# OPA_1_1.net
KiCad netlist of a schematic drawn in EAGLE
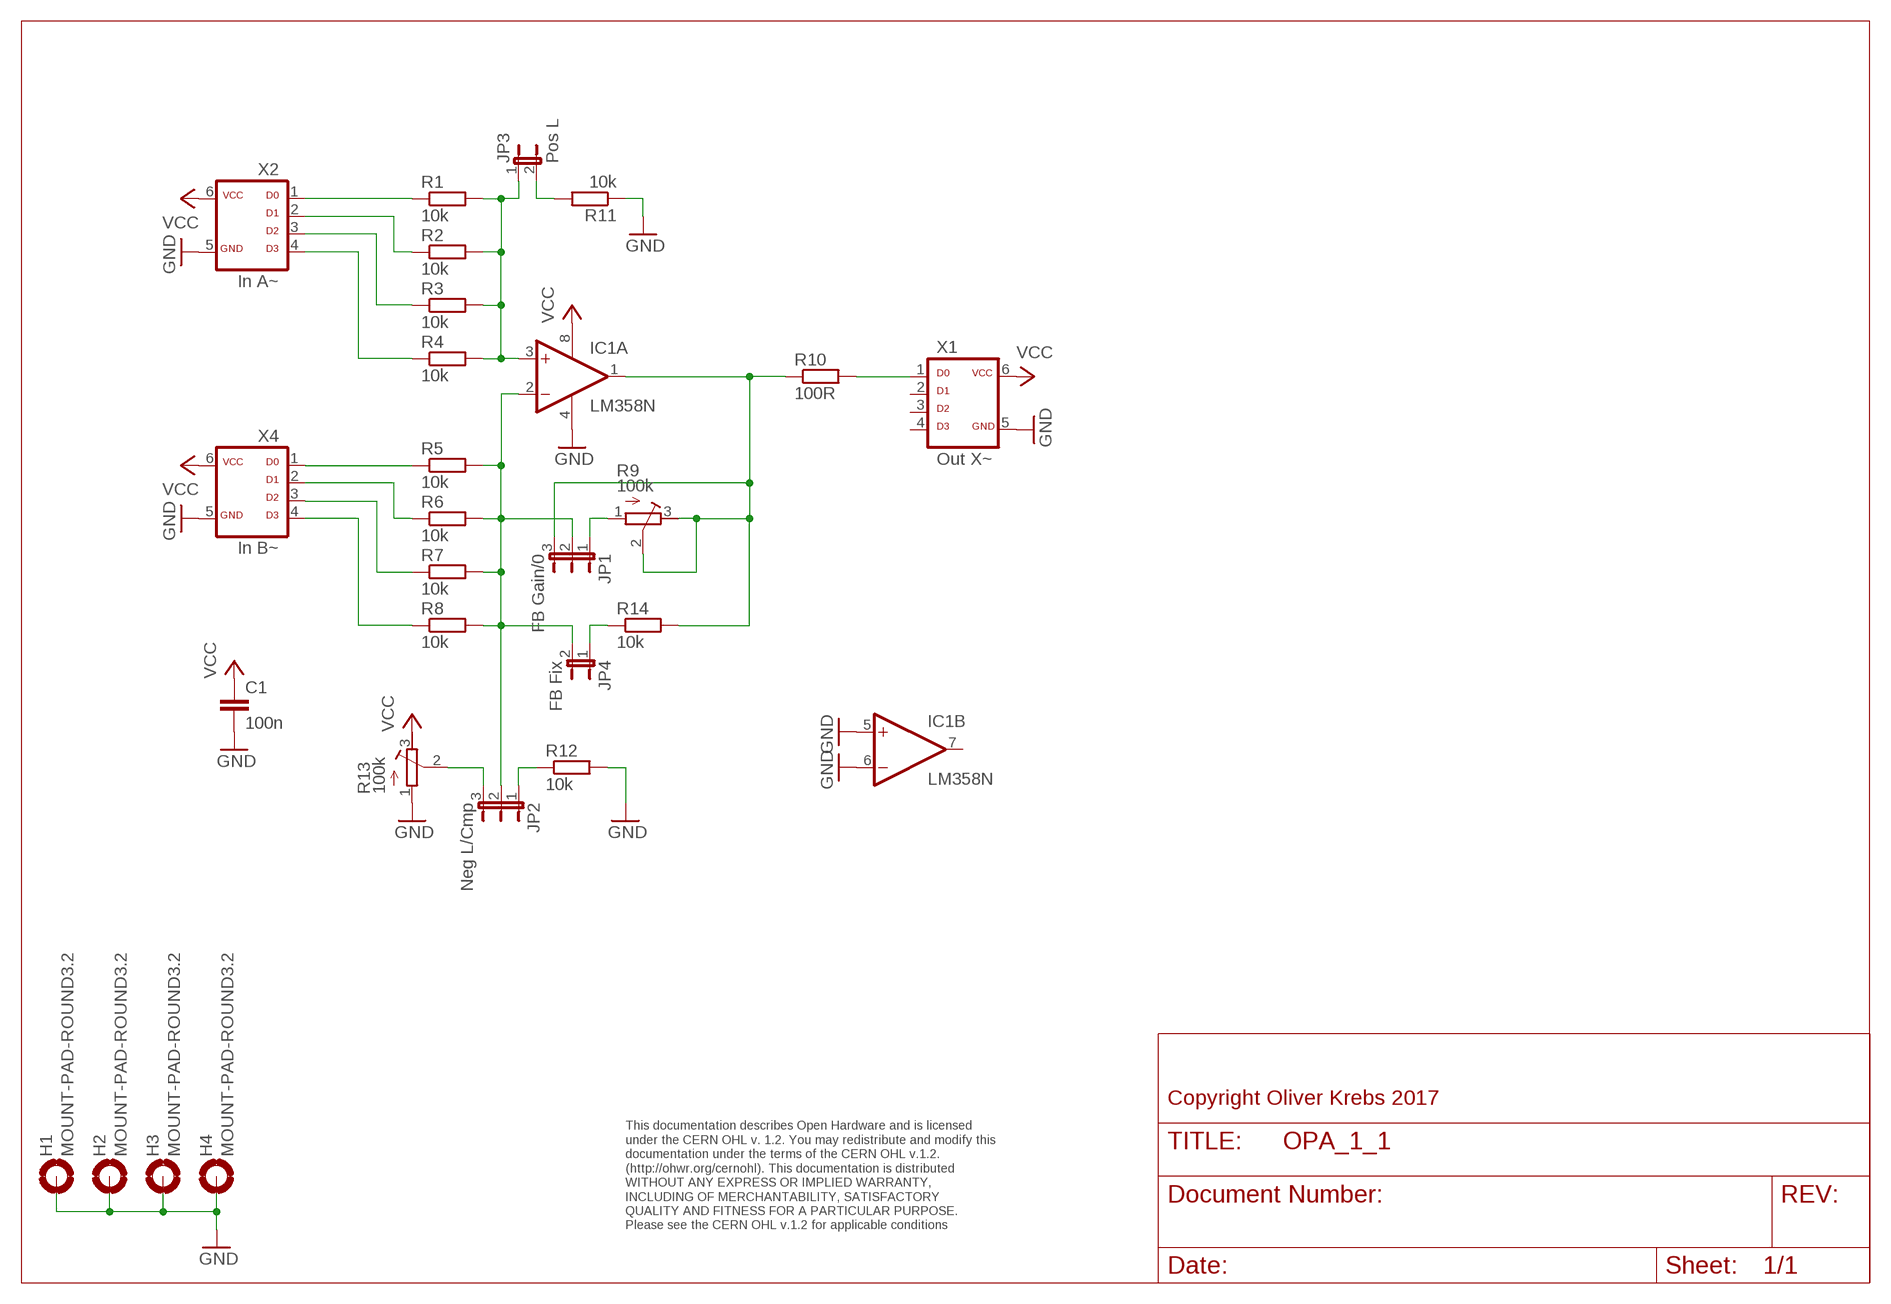
[diagram p0: schematic, sheet 1]

(export (version "E")
  (design (tool "Eeschema 10.0.6"))
  (components
    (comp (ref "C1")
      (value "100n")
      (footprint "eagle-import:C050-025X075")
      (libsource (lib "eagle-import") (part "C-EU050-025X075"))
    )
    (comp (ref "H1")
      (value "MOUNT-PAD-ROUND3.2")
      (footprint "eagle-import:3,2-PAD")
      (libsource (lib "eagle-import") (part "MOUNT-PAD-ROUND3.2"))
    )
    (comp (ref "H2")
      (value "MOUNT-PAD-ROUND3.2")
      (footprint "eagle-import:3,2-PAD")
      (libsource (lib "eagle-import") (part "MOUNT-PAD-ROUND3.2"))
    )
    (comp (ref "H3")
      (value "MOUNT-PAD-ROUND3.2")
      (footprint "eagle-import:3,2-PAD")
      (libsource (lib "eagle-import") (part "MOUNT-PAD-ROUND3.2"))
    )
    (comp (ref "H4")
      (value "MOUNT-PAD-ROUND3.2")
      (footprint "eagle-import:3,2-PAD")
      (libsource (lib "eagle-import") (part "MOUNT-PAD-ROUND3.2"))
    )
    (comp (ref "IC1")
      (value "LM358N")
      (footprint "eagle-import:DIL08")
      (libsource (lib "eagle-import") (part "LM358N"))
    )
    (comp (ref "JP1")
      (value "FB Gain/0")
      (footprint "eagle-import:JP2-U")
      (libsource (lib "eagle-import") (part "JP2EJP2-U"))
    )
    (comp (ref "JP2")
      (value "Neg L/Cmp")
      (footprint "eagle-import:JP2-U")
      (libsource (lib "eagle-import") (part "JP2EJP2-U"))
    )
    (comp (ref "JP3")
      (value "Pos L")
      (footprint "eagle-import:JP1")
      (libsource (lib "eagle-import") (part "JP1E"))
    )
    (comp (ref "JP4")
      (value "FB Fix")
      (footprint "eagle-import:JP1")
      (libsource (lib "eagle-import") (part "JP1E"))
    )
    (comp (ref "R1")
      (value "10k")
      (footprint "eagle-import:0207_10")
      (libsource (lib "eagle-import") (part "R-EU_0207/10"))
    )
    (comp (ref "R2")
      (value "10k")
      (footprint "eagle-import:0207_10")
      (libsource (lib "eagle-import") (part "R-EU_0207/10"))
    )
    (comp (ref "R3")
      (value "10k")
      (footprint "eagle-import:0207_10")
      (libsource (lib "eagle-import") (part "R-EU_0207/10"))
    )
    (comp (ref "R4")
      (value "10k")
      (footprint "eagle-import:0207_10")
      (libsource (lib "eagle-import") (part "R-EU_0207/10"))
    )
    (comp (ref "R5")
      (value "10k")
      (footprint "eagle-import:0207_10")
      (libsource (lib "eagle-import") (part "R-EU_0207/10"))
    )
    (comp (ref "R6")
      (value "10k")
      (footprint "eagle-import:0207_10")
      (libsource (lib "eagle-import") (part "R-EU_0207/10"))
    )
    (comp (ref "R7")
      (value "10k")
      (footprint "eagle-import:0207_10")
      (libsource (lib "eagle-import") (part "R-EU_0207/10"))
    )
    (comp (ref "R8")
      (value "10k")
      (footprint "eagle-import:0207_10")
      (libsource (lib "eagle-import") (part "R-EU_0207/10"))
    )
    (comp (ref "R9")
      (value "100k")
      (footprint "eagle-import:ACP-6L")
      (libsource (lib "eagle-import") (part "R-TRIMMACP"))
    )
    (comp (ref "R10")
      (value "100R")
      (footprint "eagle-import:0207_10")
      (libsource (lib "eagle-import") (part "R-EU_0207/10"))
    )
    (comp (ref "R11")
      (value "10k")
      (footprint "eagle-import:0207_10")
      (libsource (lib "eagle-import") (part "R-EU_0207/10"))
    )
    (comp (ref "R12")
      (value "10k")
      (footprint "eagle-import:0207_10")
      (libsource (lib "eagle-import") (part "R-EU_0207/10"))
    )
    (comp (ref "R13")
      (value "100k")
      (footprint "eagle-import:ACP-6L")
      (libsource (lib "eagle-import") (part "R-TRIMMACP"))
    )
    (comp (ref "R14")
      (value "10k")
      (footprint "eagle-import:0207_10")
      (libsource (lib "eagle-import") (part "R-EU_0207/10"))
    )
    (comp (ref "X1")
      (value "Out X~")
      (footprint "eagle-import:ML-6")
      (libsource (lib "eagle-import") (part "ML6D"))
    )
    (comp (ref "X2")
      (value "In A~")
      (footprint "eagle-import:ML-6")
      (libsource (lib "eagle-import") (part "ML6D"))
    )
    (comp (ref "X4")
      (value "In B~")
      (footprint "eagle-import:ML-6")
      (libsource (lib "eagle-import") (part "ML6D"))
    )
  )
  (nets
    (net (code "1") (name "GND") (class "Default")
      (node (ref "C1") (pin "2") (pinfunction "2_2") (pintype "passive"))
      (node (ref "H1") (pin "B3,2") (pinfunction "MOUNT_B3,2") (pintype "passive"))
      (node (ref "H2") (pin "B3,2") (pinfunction "MOUNT_B3,2") (pintype "passive"))
      (node (ref "H3") (pin "B3,2") (pinfunction "MOUNT_B3,2") (pintype "passive"))
      (node (ref "H4") (pin "B3,2") (pinfunction "MOUNT_B3,2") (pintype "passive"))
      (node (ref "IC1") (pin "4") (pinfunction "V-_4") (pintype "power_in"))
      (node (ref "IC1") (pin "5") (pinfunction "+IN_5") (pintype "input"))
      (node (ref "IC1") (pin "6") (pinfunction "-IN_6") (pintype "input"))
      (node (ref "R11") (pin "1") (pinfunction "1_1") (pintype "passive"))
      (node (ref "R12") (pin "2") (pinfunction "2_2") (pintype "passive"))
      (node (ref "R13") (pin "1") (pinfunction "A_1") (pintype "passive"))
      (node (ref "X1") (pin "5") (pinfunction "5_5") (pintype "passive"))
      (node (ref "X2") (pin "5") (pinfunction "5_5") (pintype "passive"))
      (node (ref "X4") (pin "5") (pinfunction "5_5") (pintype "passive"))
    )
    (net (code "2") (name "Net-(IC1A-+IN)") (class "Default")
      (node (ref "IC1") (pin "3") (pinfunction "+IN_3") (pintype "input"))
      (node (ref "JP3") (pin "1") (pinfunction "1_1") (pintype "passive"))
      (node (ref "R1") (pin "2") (pinfunction "2_2") (pintype "passive"))
      (node (ref "R2") (pin "2") (pinfunction "2_2") (pintype "passive"))
      (node (ref "R3") (pin "2") (pinfunction "2_2") (pintype "passive"))
      (node (ref "R4") (pin "2") (pinfunction "2_2") (pintype "passive"))
    )
    (net (code "3") (name "Net-(IC1A--IN)") (class "Default")
      (node (ref "IC1") (pin "2") (pinfunction "-IN_2") (pintype "input"))
      (node (ref "JP1") (pin "2") (pinfunction "2_2") (pintype "passive"))
      (node (ref "JP2") (pin "2") (pinfunction "2_2") (pintype "passive"))
      (node (ref "JP4") (pin "2") (pinfunction "2_2") (pintype "passive"))
      (node (ref "R5") (pin "2") (pinfunction "2_2") (pintype "passive"))
      (node (ref "R6") (pin "2") (pinfunction "2_2") (pintype "passive"))
      (node (ref "R7") (pin "2") (pinfunction "2_2") (pintype "passive"))
      (node (ref "R8") (pin "2") (pinfunction "2_2") (pintype "passive"))
    )
    (net (code "4") (name "Net-(IC1A-OUT)") (class "Default")
      (node (ref "IC1") (pin "1") (pinfunction "OUT_1") (pintype "output"))
      (node (ref "JP1") (pin "3") (pinfunction "3_3") (pintype "passive"))
      (node (ref "R10") (pin "1") (pinfunction "1_1") (pintype "passive"))
      (node (ref "R14") (pin "2") (pinfunction "2_2") (pintype "passive"))
      (node (ref "R9") (pin "2") (pinfunction "S_2") (pintype "passive"))
      (node (ref "R9") (pin "3") (pinfunction "E_3") (pintype "passive"))
    )
    (net (code "5") (name "Net-(JP2-Pad1)") (class "Default")
      (node (ref "JP2") (pin "1") (pinfunction "1_1") (pintype "passive"))
      (node (ref "R12") (pin "1") (pinfunction "1_1") (pintype "passive"))
    )
    (net (code "6") (name "Net-(JP3-Pad2)") (class "Default")
      (node (ref "JP3") (pin "2") (pinfunction "2_2") (pintype "passive"))
      (node (ref "R11") (pin "2") (pinfunction "2_2") (pintype "passive"))
    )
    (net (code "7") (name "Net-(JP4-Pad1)") (class "Default")
      (node (ref "JP4") (pin "1") (pinfunction "1_1") (pintype "passive"))
      (node (ref "R14") (pin "1") (pinfunction "1_1") (pintype "passive"))
    )
    (net (code "8") (name "Net-(R1-Pad1)") (class "Default")
      (node (ref "R1") (pin "1") (pinfunction "1_1") (pintype "passive"))
      (node (ref "X2") (pin "1") (pinfunction "1_1") (pintype "passive"))
    )
    (net (code "9") (name "Net-(R2-Pad1)") (class "Default")
      (node (ref "R2") (pin "1") (pinfunction "1_1") (pintype "passive"))
      (node (ref "X2") (pin "2") (pinfunction "2_2") (pintype "passive"))
    )
    (net (code "10") (name "Net-(R3-Pad1)") (class "Default")
      (node (ref "R3") (pin "1") (pinfunction "1_1") (pintype "passive"))
      (node (ref "X2") (pin "3") (pinfunction "3_3") (pintype "passive"))
    )
    (net (code "11") (name "Net-(R4-Pad1)") (class "Default")
      (node (ref "R4") (pin "1") (pinfunction "1_1") (pintype "passive"))
      (node (ref "X2") (pin "4") (pinfunction "4_4") (pintype "passive"))
    )
    (net (code "12") (name "Net-(R5-Pad1)") (class "Default")
      (node (ref "R5") (pin "1") (pinfunction "1_1") (pintype "passive"))
      (node (ref "X4") (pin "1") (pinfunction "1_1") (pintype "passive"))
    )
    (net (code "13") (name "Net-(R6-Pad1)") (class "Default")
      (node (ref "R6") (pin "1") (pinfunction "1_1") (pintype "passive"))
      (node (ref "X4") (pin "2") (pinfunction "2_2") (pintype "passive"))
    )
    (net (code "14") (name "Net-(R7-Pad1)") (class "Default")
      (node (ref "R7") (pin "1") (pinfunction "1_1") (pintype "passive"))
      (node (ref "X4") (pin "3") (pinfunction "3_3") (pintype "passive"))
    )
    (net (code "15") (name "Net-(R8-Pad1)") (class "Default")
      (node (ref "R8") (pin "1") (pinfunction "1_1") (pintype "passive"))
      (node (ref "X4") (pin "4") (pinfunction "4_4") (pintype "passive"))
    )
    (net (code "16") (name "Net-(R9-A)") (class "Default")
      (node (ref "JP1") (pin "1") (pinfunction "1_1") (pintype "passive"))
      (node (ref "R9") (pin "1") (pinfunction "A_1") (pintype "passive"))
    )
    (net (code "17") (name "Net-(R10-Pad2)") (class "Default")
      (node (ref "R10") (pin "2") (pinfunction "2_2") (pintype "passive"))
      (node (ref "X1") (pin "1") (pinfunction "1_1") (pintype "passive"))
    )
    (net (code "18") (name "Net-(R13-S)") (class "Default")
      (node (ref "JP2") (pin "3") (pinfunction "3_3") (pintype "passive"))
      (node (ref "R13") (pin "2") (pinfunction "S_2") (pintype "passive"))
    )
    (net (code "19") (name "VCC") (class "Default")
      (node (ref "C1") (pin "1") (pinfunction "1_1") (pintype "passive"))
      (node (ref "IC1") (pin "8") (pinfunction "V+_8") (pintype "power_in"))
      (node (ref "R13") (pin "3") (pinfunction "E_3") (pintype "passive"))
      (node (ref "X1") (pin "6") (pinfunction "6_6") (pintype "passive"))
      (node (ref "X2") (pin "6") (pinfunction "6_6") (pintype "passive"))
      (node (ref "X4") (pin "6") (pinfunction "6_6") (pintype "passive"))
    )
    (net (code "20") (name "unconnected-(IC1B-OUT-Pad7)") (class "Default")
      (node (ref "IC1") (pin "7") (pinfunction "OUT_7") (pintype "output"))
    )
    (net (code "21") (name "unconnected-(X1-Pad2)") (class "Default")
      (node (ref "X1") (pin "2") (pinfunction "2_2") (pintype "passive"))
    )
    (net (code "22") (name "unconnected-(X1-Pad3)") (class "Default")
      (node (ref "X1") (pin "3") (pinfunction "3_3") (pintype "passive"))
    )
    (net (code "23") (name "unconnected-(X1-Pad4)") (class "Default")
      (node (ref "X1") (pin "4") (pinfunction "4_4") (pintype "passive"))
    )
  )
)
